# DSKY_DISP.net
KiCad netlist of a schematic drawn in EAGLE
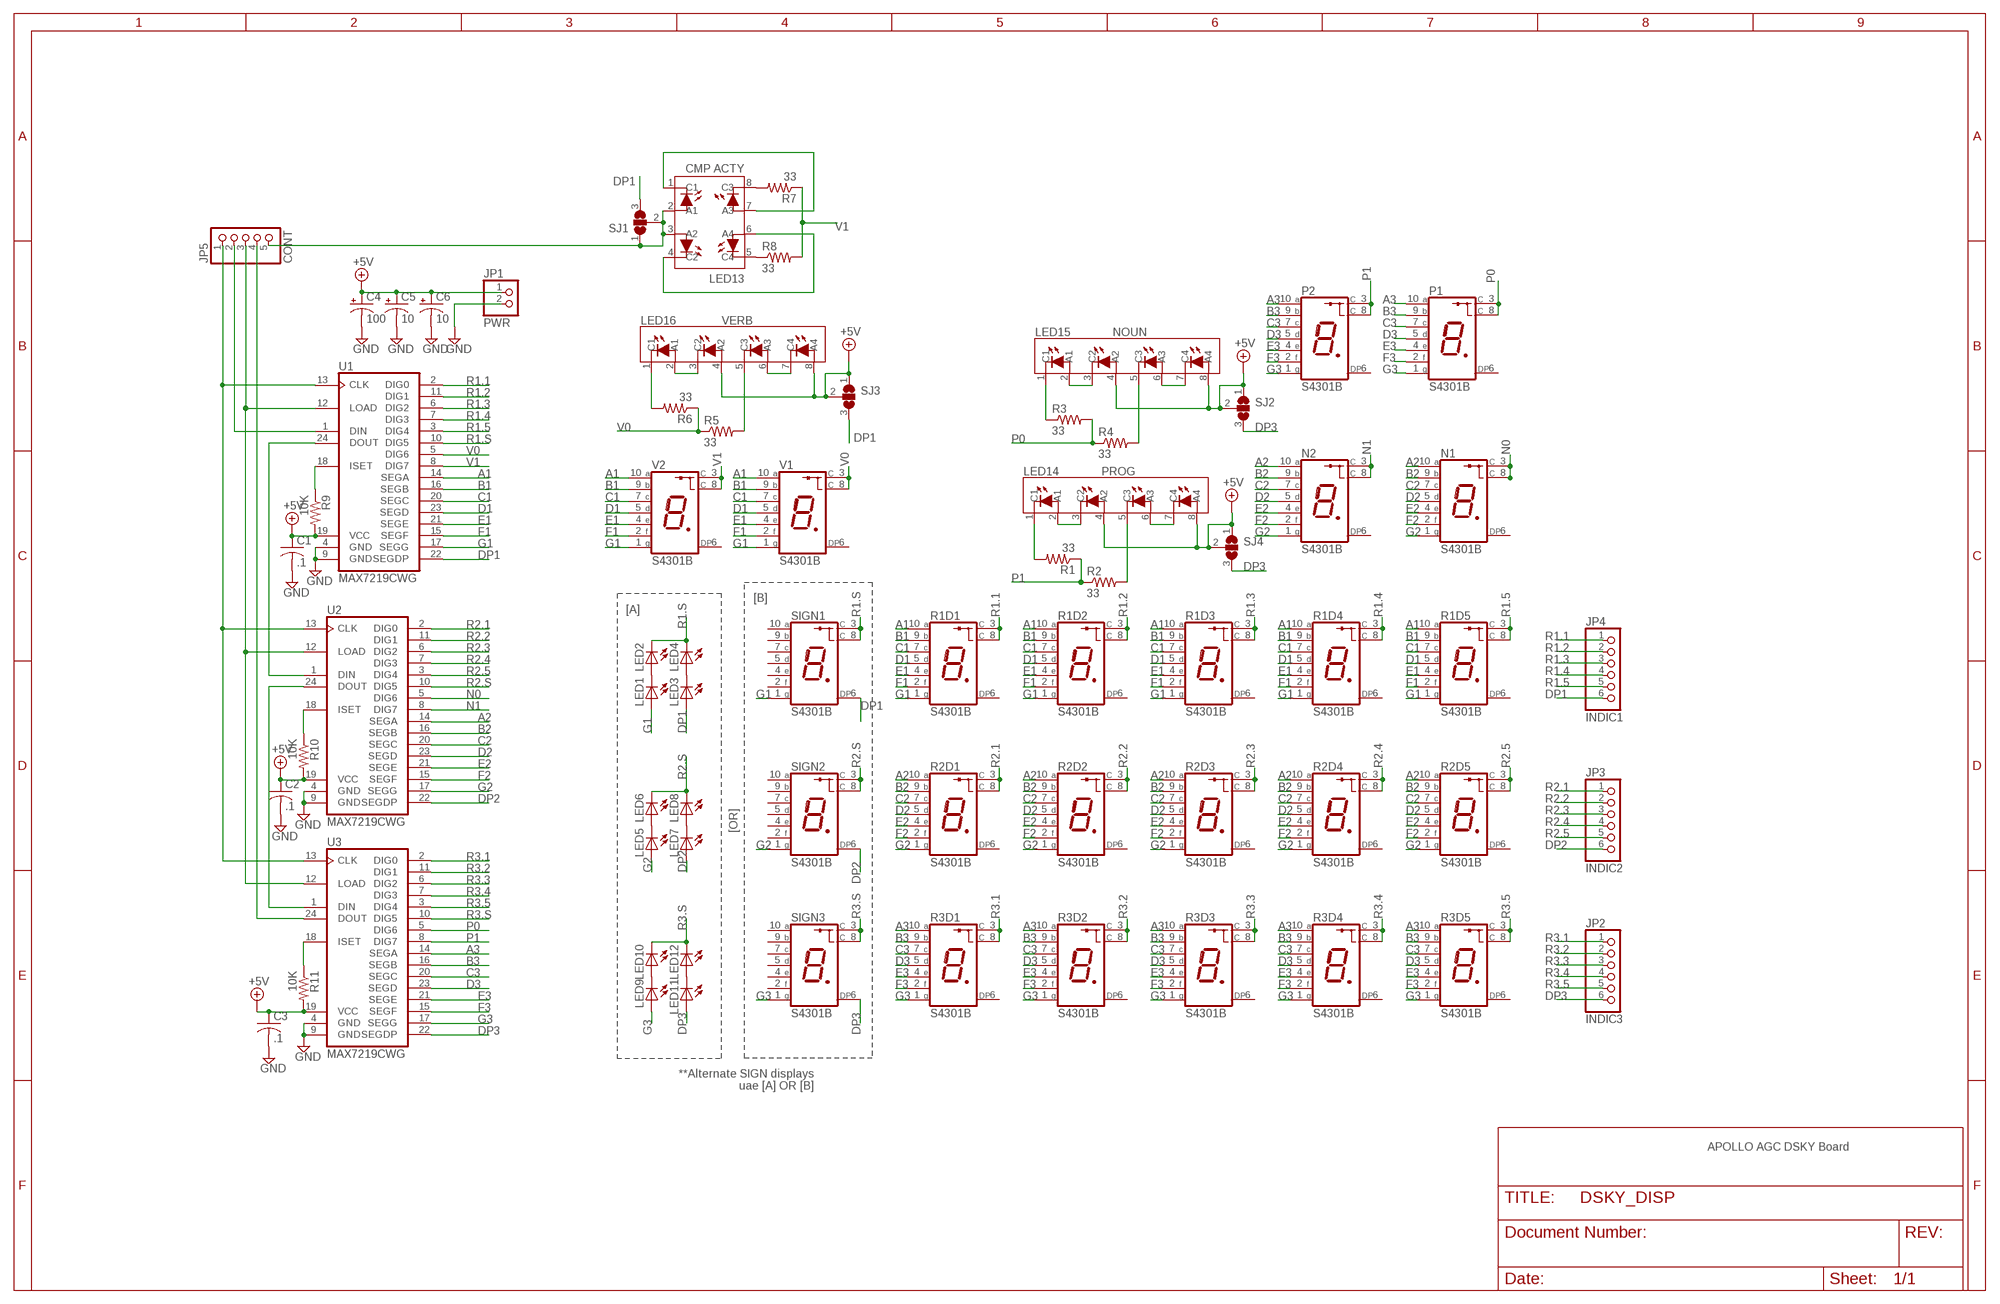
[diagram p0: schematic, sheet 1]

(export (version "E")
  (design (tool "Eeschema 10.0.6"))
  (components
    (comp (ref "C1")
      (value ".1")
      (footprint "eagle-import:C025-030X050")
      (libsource (lib "eagle-import") (part "C-US025-030X050"))
    )
    (comp (ref "C2")
      (value ".1")
      (footprint "eagle-import:C025-030X050")
      (libsource (lib "eagle-import") (part "C-US025-030X050"))
    )
    (comp (ref "C3")
      (value ".1")
      (footprint "eagle-import:C025-030X050")
      (libsource (lib "eagle-import") (part "C-US025-030X050"))
    )
    (comp (ref "C4")
      (value "100")
      (footprint "eagle-import:E2,5-6E")
      (libsource (lib "eagle-import") (part "CPOL-USE2,5-6E"))
    )
    (comp (ref "C5")
      (value "10")
      (footprint "eagle-import:E1,8-4")
      (libsource (lib "eagle-import") (part "CPOL-USE1.8-4"))
    )
    (comp (ref "C6")
      (value "10")
      (footprint "eagle-import:E1,8-4")
      (libsource (lib "eagle-import") (part "CPOL-USE1.8-4"))
    )
    (comp (ref "JP1")
      (value "PWR")
      (footprint "eagle-import:1X02")
      (libsource (lib "eagle-import") (part "PINHD-1X2"))
    )
    (comp (ref "JP2")
      (value "INDIC3")
      (footprint "eagle-import:1X06")
      (libsource (lib "eagle-import") (part "PINHD-1X6"))
    )
    (comp (ref "JP3")
      (value "INDIC2")
      (footprint "eagle-import:1X06")
      (libsource (lib "eagle-import") (part "PINHD-1X6"))
    )
    (comp (ref "JP4")
      (value "INDIC1")
      (footprint "eagle-import:1X06")
      (libsource (lib "eagle-import") (part "PINHD-1X6"))
    )
    (comp (ref "JP5")
      (value "CONT")
      (footprint "eagle-import:1X05")
      (libsource (lib "eagle-import") (part "PINHD-1X5"))
    )
    (comp (ref "LED1")
      (value "LEDCHIPLED_0603")
      (footprint "eagle-import:CHIPLED_0603")
      (libsource (lib "eagle-import") (part "LEDCHIPLED_0603"))
    )
    (comp (ref "LED2")
      (value "LEDCHIPLED_0603")
      (footprint "eagle-import:CHIPLED_0603")
      (libsource (lib "eagle-import") (part "LEDCHIPLED_0603"))
    )
    (comp (ref "LED3")
      (value "LEDCHIPLED_0603")
      (footprint "eagle-import:CHIPLED_0603")
      (libsource (lib "eagle-import") (part "LEDCHIPLED_0603"))
    )
    (comp (ref "LED4")
      (value "LEDCHIPLED_0603")
      (footprint "eagle-import:CHIPLED_0603")
      (libsource (lib "eagle-import") (part "LEDCHIPLED_0603"))
    )
    (comp (ref "LED5")
      (value "LEDCHIPLED_0603")
      (footprint "eagle-import:CHIPLED_0603")
      (libsource (lib "eagle-import") (part "LEDCHIPLED_0603"))
    )
    (comp (ref "LED6")
      (value "LEDCHIPLED_0603")
      (footprint "eagle-import:CHIPLED_0603")
      (libsource (lib "eagle-import") (part "LEDCHIPLED_0603"))
    )
    (comp (ref "LED7")
      (value "LEDCHIPLED_0603")
      (footprint "eagle-import:CHIPLED_0603")
      (libsource (lib "eagle-import") (part "LEDCHIPLED_0603"))
    )
    (comp (ref "LED8")
      (value "LEDCHIPLED_0603")
      (footprint "eagle-import:CHIPLED_0603")
      (libsource (lib "eagle-import") (part "LEDCHIPLED_0603"))
    )
    (comp (ref "LED9")
      (value "LEDCHIPLED_0603")
      (footprint "eagle-import:CHIPLED_0603")
      (libsource (lib "eagle-import") (part "LEDCHIPLED_0603"))
    )
    (comp (ref "LED10")
      (value "LEDCHIPLED_0603")
      (footprint "eagle-import:CHIPLED_0603")
      (libsource (lib "eagle-import") (part "LEDCHIPLED_0603"))
    )
    (comp (ref "LED11")
      (value "LEDCHIPLED_0603")
      (footprint "eagle-import:CHIPLED_0603")
      (libsource (lib "eagle-import") (part "LEDCHIPLED_0603"))
    )
    (comp (ref "LED12")
      (value "LEDCHIPLED_0603")
      (footprint "eagle-import:CHIPLED_0603")
      (libsource (lib "eagle-import") (part "LEDCHIPLED_0603"))
    )
    (comp (ref "LED13")
      (value "CMP ACTY")
      (footprint "eagle-import:SOCKET-08")
      (libsource (lib "eagle-import") (part "HCLP-HLMP-2855"))
    )
    (comp (ref "LED14")
      (value "PROG")
      (footprint "eagle-import:SIP-08")
      (libsource (lib "eagle-import") (part "HLMP-2655"))
    )
    (comp (ref "LED15")
      (value "NOUN")
      (footprint "eagle-import:SIP-08")
      (libsource (lib "eagle-import") (part "HLMP-2655"))
    )
    (comp (ref "LED16")
      (value "VERB")
      (footprint "eagle-import:SIP-08")
      (libsource (lib "eagle-import") (part "HLMP-2655"))
    )
    (comp (ref "N1")
      (value "S4301B")
      (footprint "eagle-import:S4301B")
      (libsource (lib "eagle-import") (part "S4301B"))
    )
    (comp (ref "N2")
      (value "S4301B")
      (footprint "eagle-import:S4301B")
      (libsource (lib "eagle-import") (part "S4301B"))
    )
    (comp (ref "P1")
      (value "S4301B")
      (footprint "eagle-import:S4301B")
      (libsource (lib "eagle-import") (part "S4301B"))
    )
    (comp (ref "P2")
      (value "S4301B")
      (footprint "eagle-import:S4301B")
      (libsource (lib "eagle-import") (part "S4301B"))
    )
    (comp (ref "R1")
      (value "33")
      (footprint "eagle-import:0207_10")
      (libsource (lib "eagle-import") (part "R-US_0207/10"))
    )
    (comp (ref "R1D1")
      (value "S4301B")
      (footprint "eagle-import:S4301B")
      (libsource (lib "eagle-import") (part "S4301B"))
    )
    (comp (ref "R1D2")
      (value "S4301B")
      (footprint "eagle-import:S4301B")
      (libsource (lib "eagle-import") (part "S4301B"))
    )
    (comp (ref "R1D3")
      (value "S4301B")
      (footprint "eagle-import:S4301B")
      (libsource (lib "eagle-import") (part "S4301B"))
    )
    (comp (ref "R1D4")
      (value "S4301B")
      (footprint "eagle-import:S4301B")
      (libsource (lib "eagle-import") (part "S4301B"))
    )
    (comp (ref "R1D5")
      (value "S4301B")
      (footprint "eagle-import:S4301B")
      (libsource (lib "eagle-import") (part "S4301B"))
    )
    (comp (ref "R2")
      (value "33")
      (footprint "eagle-import:0207_10")
      (libsource (lib "eagle-import") (part "R-US_0207/10"))
    )
    (comp (ref "R2D1")
      (value "S4301B")
      (footprint "eagle-import:S4301B")
      (libsource (lib "eagle-import") (part "S4301B"))
    )
    (comp (ref "R2D2")
      (value "S4301B")
      (footprint "eagle-import:S4301B")
      (libsource (lib "eagle-import") (part "S4301B"))
    )
    (comp (ref "R2D3")
      (value "S4301B")
      (footprint "eagle-import:S4301B")
      (libsource (lib "eagle-import") (part "S4301B"))
    )
    (comp (ref "R2D4")
      (value "S4301B")
      (footprint "eagle-import:S4301B")
      (libsource (lib "eagle-import") (part "S4301B"))
    )
    (comp (ref "R2D5")
      (value "S4301B")
      (footprint "eagle-import:S4301B")
      (libsource (lib "eagle-import") (part "S4301B"))
    )
    (comp (ref "R3")
      (value "33")
      (footprint "eagle-import:0207_10")
      (libsource (lib "eagle-import") (part "R-US_0207/10"))
    )
    (comp (ref "R3D1")
      (value "S4301B")
      (footprint "eagle-import:S4301B")
      (libsource (lib "eagle-import") (part "S4301B"))
    )
    (comp (ref "R3D2")
      (value "S4301B")
      (footprint "eagle-import:S4301B")
      (libsource (lib "eagle-import") (part "S4301B"))
    )
    (comp (ref "R3D3")
      (value "S4301B")
      (footprint "eagle-import:S4301B")
      (libsource (lib "eagle-import") (part "S4301B"))
    )
    (comp (ref "R3D4")
      (value "S4301B")
      (footprint "eagle-import:S4301B")
      (libsource (lib "eagle-import") (part "S4301B"))
    )
    (comp (ref "R3D5")
      (value "S4301B")
      (footprint "eagle-import:S4301B")
      (libsource (lib "eagle-import") (part "S4301B"))
    )
    (comp (ref "R4")
      (value "33")
      (footprint "eagle-import:0207_10")
      (libsource (lib "eagle-import") (part "R-US_0207/10"))
    )
    (comp (ref "R5")
      (value "33")
      (footprint "eagle-import:0207_10")
      (libsource (lib "eagle-import") (part "R-US_0207/10"))
    )
    (comp (ref "R6")
      (value "33")
      (footprint "eagle-import:0207_10")
      (libsource (lib "eagle-import") (part "R-US_0207/10"))
    )
    (comp (ref "R7")
      (value "33")
      (footprint "eagle-import:0207_10")
      (libsource (lib "eagle-import") (part "R-US_0207/10"))
    )
    (comp (ref "R8")
      (value "33")
      (footprint "eagle-import:0207_10")
      (libsource (lib "eagle-import") (part "R-US_0207/10"))
    )
    (comp (ref "R9")
      (value "10K")
      (footprint "eagle-import:0207_10")
      (libsource (lib "eagle-import") (part "R-US_0207/10"))
    )
    (comp (ref "R10")
      (value "10K")
      (footprint "eagle-import:0207_10")
      (libsource (lib "eagle-import") (part "R-US_0207/10"))
    )
    (comp (ref "R11")
      (value "10K")
      (footprint "eagle-import:0207_10")
      (libsource (lib "eagle-import") (part "R-US_0207/10"))
    )
    (comp (ref "SIGN1")
      (value "S4301B")
      (footprint "eagle-import:S4301B")
      (libsource (lib "eagle-import") (part "S4301B"))
    )
    (comp (ref "SIGN2")
      (value "S4301B")
      (footprint "eagle-import:S4301B")
      (libsource (lib "eagle-import") (part "S4301B"))
    )
    (comp (ref "SIGN3")
      (value "S4301B")
      (footprint "eagle-import:S4301B")
      (libsource (lib "eagle-import") (part "S4301B"))
    )
    (comp (ref "SJ1")
      (value "SJ2WW")
      (footprint "eagle-import:SJ_2W")
      (libsource (lib "eagle-import") (part "SJ2WW"))
    )
    (comp (ref "SJ2")
      (value "SJ2WW")
      (footprint "eagle-import:SJ_2W")
      (libsource (lib "eagle-import") (part "SJ2WW"))
    )
    (comp (ref "SJ3")
      (value "SJ2WW")
      (footprint "eagle-import:SJ_2W")
      (libsource (lib "eagle-import") (part "SJ2WW"))
    )
    (comp (ref "SJ4")
      (value "SJ2WW")
      (footprint "eagle-import:SJ_2W")
      (libsource (lib "eagle-import") (part "SJ2WW"))
    )
    (comp (ref "U1")
      (value "MAX7219CWG")
      (footprint "eagle-import:SO24W")
      (libsource (lib "eagle-import") (part "MAX7219WGC"))
    )
    (comp (ref "U2")
      (value "MAX7219CWG")
      (footprint "eagle-import:SO24W")
      (libsource (lib "eagle-import") (part "MAX7219WGC"))
    )
    (comp (ref "U3")
      (value "MAX7219CWG")
      (footprint "eagle-import:SO24W")
      (libsource (lib "eagle-import") (part "MAX7219WGC"))
    )
    (comp (ref "V1")
      (value "S4301B")
      (footprint "eagle-import:S4301B")
      (libsource (lib "eagle-import") (part "S4301B"))
    )
    (comp (ref "V2")
      (value "S4301B")
      (footprint "eagle-import:S4301B")
      (libsource (lib "eagle-import") (part "S4301B"))
    )
  )
  (nets
    (net (code "1") (name "+5V") (class "Default")
      (node (ref "C1") (pin "1") (pinfunction "1_1") (pintype "passive"))
      (node (ref "C2") (pin "1") (pinfunction "1_1") (pintype "passive"))
      (node (ref "C3") (pin "1") (pinfunction "1_1") (pintype "passive"))
      (node (ref "C4") (pin "+") (pinfunction "+_+") (pintype "passive"))
      (node (ref "C5") (pin "+") (pinfunction "+_+") (pintype "passive"))
      (node (ref "C6") (pin "+") (pinfunction "+_+") (pintype "passive"))
      (node (ref "JP1") (pin "1") (pinfunction "1_1") (pintype "passive"))
      (node (ref "LED14") (pin "4") (pinfunction "A2_4") (pintype "passive"))
      (node (ref "LED14") (pin "8") (pinfunction "A4_8") (pintype "passive"))
      (node (ref "LED15") (pin "4") (pinfunction "A2_4") (pintype "passive"))
      (node (ref "LED15") (pin "8") (pinfunction "A4_8") (pintype "passive"))
      (node (ref "LED16") (pin "4") (pinfunction "A2_4") (pintype "passive"))
      (node (ref "LED16") (pin "8") (pinfunction "A4_8") (pintype "passive"))
      (node (ref "R10") (pin "2") (pinfunction "2_2") (pintype "passive"))
      (node (ref "R11") (pin "2") (pinfunction "2_2") (pintype "passive"))
      (node (ref "R9") (pin "2") (pinfunction "2_2") (pintype "passive"))
      (node (ref "SJ2") (pin "1") (pinfunction "1_1") (pintype "passive"))
      (node (ref "SJ2") (pin "2") (pinfunction "2_2") (pintype "passive"))
      (node (ref "SJ3") (pin "1") (pinfunction "1_1") (pintype "passive"))
      (node (ref "SJ3") (pin "2") (pinfunction "2_2") (pintype "passive"))
      (node (ref "SJ4") (pin "1") (pinfunction "1_1") (pintype "passive"))
      (node (ref "SJ4") (pin "2") (pinfunction "2_2") (pintype "passive"))
      (node (ref "U1") (pin "19") (pinfunction "VCC_19") (pintype "power_in"))
      (node (ref "U2") (pin "19") (pinfunction "VCC_19") (pintype "power_in"))
      (node (ref "U3") (pin "19") (pinfunction "VCC_19") (pintype "power_in"))
    )
    (net (code "2") (name "/A1") (class "Default")
      (node (ref "R1D1") (pin "10") (pinfunction "A_10") (pintype "passive"))
      (node (ref "R1D2") (pin "10") (pinfunction "A_10") (pintype "passive"))
      (node (ref "R1D3") (pin "10") (pinfunction "A_10") (pintype "passive"))
      (node (ref "R1D4") (pin "10") (pinfunction "A_10") (pintype "passive"))
      (node (ref "R1D5") (pin "10") (pinfunction "A_10") (pintype "passive"))
      (node (ref "U1") (pin "14") (pinfunction "SEGA_14") (pintype "output"))
      (node (ref "V1") (pin "10") (pinfunction "A_10") (pintype "passive"))
      (node (ref "V2") (pin "10") (pinfunction "A_10") (pintype "passive"))
    )
    (net (code "3") (name "/A2") (class "Default")
      (node (ref "N1") (pin "10") (pinfunction "A_10") (pintype "passive"))
      (node (ref "N2") (pin "10") (pinfunction "A_10") (pintype "passive"))
      (node (ref "R2D1") (pin "10") (pinfunction "A_10") (pintype "passive"))
      (node (ref "R2D2") (pin "10") (pinfunction "A_10") (pintype "passive"))
      (node (ref "R2D3") (pin "10") (pinfunction "A_10") (pintype "passive"))
      (node (ref "R2D4") (pin "10") (pinfunction "A_10") (pintype "passive"))
      (node (ref "R2D5") (pin "10") (pinfunction "A_10") (pintype "passive"))
      (node (ref "U2") (pin "14") (pinfunction "SEGA_14") (pintype "output"))
    )
    (net (code "4") (name "/A3") (class "Default")
      (node (ref "P1") (pin "10") (pinfunction "A_10") (pintype "passive"))
      (node (ref "P2") (pin "10") (pinfunction "A_10") (pintype "passive"))
      (node (ref "R3D1") (pin "10") (pinfunction "A_10") (pintype "passive"))
      (node (ref "R3D2") (pin "10") (pinfunction "A_10") (pintype "passive"))
      (node (ref "R3D3") (pin "10") (pinfunction "A_10") (pintype "passive"))
      (node (ref "R3D4") (pin "10") (pinfunction "A_10") (pintype "passive"))
      (node (ref "R3D5") (pin "10") (pinfunction "A_10") (pintype "passive"))
      (node (ref "U3") (pin "14") (pinfunction "SEGA_14") (pintype "output"))
    )
    (net (code "5") (name "/B1") (class "Default")
      (node (ref "R1D1") (pin "9") (pinfunction "B_9") (pintype "passive"))
      (node (ref "R1D2") (pin "9") (pinfunction "B_9") (pintype "passive"))
      (node (ref "R1D3") (pin "9") (pinfunction "B_9") (pintype "passive"))
      (node (ref "R1D4") (pin "9") (pinfunction "B_9") (pintype "passive"))
      (node (ref "R1D5") (pin "9") (pinfunction "B_9") (pintype "passive"))
      (node (ref "U1") (pin "16") (pinfunction "SEGB_16") (pintype "output"))
      (node (ref "V1") (pin "9") (pinfunction "B_9") (pintype "passive"))
      (node (ref "V2") (pin "9") (pinfunction "B_9") (pintype "passive"))
    )
    (net (code "6") (name "/B2") (class "Default")
      (node (ref "N1") (pin "9") (pinfunction "B_9") (pintype "passive"))
      (node (ref "N2") (pin "9") (pinfunction "B_9") (pintype "passive"))
      (node (ref "R2D1") (pin "9") (pinfunction "B_9") (pintype "passive"))
      (node (ref "R2D2") (pin "9") (pinfunction "B_9") (pintype "passive"))
      (node (ref "R2D3") (pin "9") (pinfunction "B_9") (pintype "passive"))
      (node (ref "R2D4") (pin "9") (pinfunction "B_9") (pintype "passive"))
      (node (ref "R2D5") (pin "9") (pinfunction "B_9") (pintype "passive"))
      (node (ref "U2") (pin "16") (pinfunction "SEGB_16") (pintype "output"))
    )
    (net (code "7") (name "/B3") (class "Default")
      (node (ref "P1") (pin "9") (pinfunction "B_9") (pintype "passive"))
      (node (ref "P2") (pin "9") (pinfunction "B_9") (pintype "passive"))
      (node (ref "R3D1") (pin "9") (pinfunction "B_9") (pintype "passive"))
      (node (ref "R3D2") (pin "9") (pinfunction "B_9") (pintype "passive"))
      (node (ref "R3D3") (pin "9") (pinfunction "B_9") (pintype "passive"))
      (node (ref "R3D4") (pin "9") (pinfunction "B_9") (pintype "passive"))
      (node (ref "R3D5") (pin "9") (pinfunction "B_9") (pintype "passive"))
      (node (ref "U3") (pin "16") (pinfunction "SEGB_16") (pintype "output"))
    )
    (net (code "8") (name "/C1") (class "Default")
      (node (ref "R1D1") (pin "7") (pinfunction "C_7") (pintype "passive"))
      (node (ref "R1D2") (pin "7") (pinfunction "C_7") (pintype "passive"))
      (node (ref "R1D3") (pin "7") (pinfunction "C_7") (pintype "passive"))
      (node (ref "R1D4") (pin "7") (pinfunction "C_7") (pintype "passive"))
      (node (ref "R1D5") (pin "7") (pinfunction "C_7") (pintype "passive"))
      (node (ref "U1") (pin "20") (pinfunction "SEGC_20") (pintype "output"))
      (node (ref "V1") (pin "7") (pinfunction "C_7") (pintype "passive"))
      (node (ref "V2") (pin "7") (pinfunction "C_7") (pintype "passive"))
    )
    (net (code "9") (name "/C2") (class "Default")
      (node (ref "N1") (pin "7") (pinfunction "C_7") (pintype "passive"))
      (node (ref "N2") (pin "7") (pinfunction "C_7") (pintype "passive"))
      (node (ref "R2D1") (pin "7") (pinfunction "C_7") (pintype "passive"))
      (node (ref "R2D2") (pin "7") (pinfunction "C_7") (pintype "passive"))
      (node (ref "R2D3") (pin "7") (pinfunction "C_7") (pintype "passive"))
      (node (ref "R2D4") (pin "7") (pinfunction "C_7") (pintype "passive"))
      (node (ref "R2D5") (pin "7") (pinfunction "C_7") (pintype "passive"))
      (node (ref "U2") (pin "20") (pinfunction "SEGC_20") (pintype "output"))
    )
    (net (code "10") (name "/C3") (class "Default")
      (node (ref "P1") (pin "7") (pinfunction "C_7") (pintype "passive"))
      (node (ref "P2") (pin "7") (pinfunction "C_7") (pintype "passive"))
      (node (ref "R3D1") (pin "7") (pinfunction "C_7") (pintype "passive"))
      (node (ref "R3D2") (pin "7") (pinfunction "C_7") (pintype "passive"))
      (node (ref "R3D3") (pin "7") (pinfunction "C_7") (pintype "passive"))
      (node (ref "R3D4") (pin "7") (pinfunction "C_7") (pintype "passive"))
      (node (ref "R3D5") (pin "7") (pinfunction "C_7") (pintype "passive"))
      (node (ref "U3") (pin "20") (pinfunction "SEGC_20") (pintype "output"))
    )
    (net (code "11") (name "/D1") (class "Default")
      (node (ref "R1D1") (pin "5") (pinfunction "D_5") (pintype "passive"))
      (node (ref "R1D2") (pin "5") (pinfunction "D_5") (pintype "passive"))
      (node (ref "R1D3") (pin "5") (pinfunction "D_5") (pintype "passive"))
      (node (ref "R1D4") (pin "5") (pinfunction "D_5") (pintype "passive"))
      (node (ref "R1D5") (pin "5") (pinfunction "D_5") (pintype "passive"))
      (node (ref "U1") (pin "23") (pinfunction "SEGD_23") (pintype "output"))
      (node (ref "V1") (pin "5") (pinfunction "D_5") (pintype "passive"))
      (node (ref "V2") (pin "5") (pinfunction "D_5") (pintype "passive"))
    )
    (net (code "12") (name "/D2") (class "Default")
      (node (ref "N1") (pin "5") (pinfunction "D_5") (pintype "passive"))
      (node (ref "N2") (pin "5") (pinfunction "D_5") (pintype "passive"))
      (node (ref "R2D1") (pin "5") (pinfunction "D_5") (pintype "passive"))
      (node (ref "R2D2") (pin "5") (pinfunction "D_5") (pintype "passive"))
      (node (ref "R2D3") (pin "5") (pinfunction "D_5") (pintype "passive"))
      (node (ref "R2D4") (pin "5") (pinfunction "D_5") (pintype "passive"))
      (node (ref "R2D5") (pin "5") (pinfunction "D_5") (pintype "passive"))
      (node (ref "U2") (pin "23") (pinfunction "SEGD_23") (pintype "output"))
    )
    (net (code "13") (name "/D3") (class "Default")
      (node (ref "P1") (pin "5") (pinfunction "D_5") (pintype "passive"))
      (node (ref "P2") (pin "5") (pinfunction "D_5") (pintype "passive"))
      (node (ref "R3D1") (pin "5") (pinfunction "D_5") (pintype "passive"))
      (node (ref "R3D2") (pin "5") (pinfunction "D_5") (pintype "passive"))
      (node (ref "R3D3") (pin "5") (pinfunction "D_5") (pintype "passive"))
      (node (ref "R3D4") (pin "5") (pinfunction "D_5") (pintype "passive"))
      (node (ref "R3D5") (pin "5") (pinfunction "D_5") (pintype "passive"))
      (node (ref "U3") (pin "23") (pinfunction "SEGD_23") (pintype "output"))
    )
    (net (code "14") (name "/DP1") (class "Default")
      (node (ref "JP4") (pin "6") (pinfunction "6_6") (pintype "passive"))
      (node (ref "LED3") (pin "A") (pinfunction "A_A") (pintype "passive"))
      (node (ref "SIGN1") (pin "6") (pinfunction "DP_6") (pintype "passive"))
      (node (ref "SJ1") (pin "3") (pinfunction "3_3") (pintype "passive"))
      (node (ref "SJ3") (pin "3") (pinfunction "3_3") (pintype "passive"))
      (node (ref "U1") (pin "22") (pinfunction "SEGDP_22") (pintype "output"))
    )
    (net (code "15") (name "/DP2") (class "Default")
      (node (ref "JP3") (pin "6") (pinfunction "6_6") (pintype "passive"))
      (node (ref "LED7") (pin "A") (pinfunction "A_A") (pintype "passive"))
      (node (ref "SIGN2") (pin "6") (pinfunction "DP_6") (pintype "passive"))
      (node (ref "U2") (pin "22") (pinfunction "SEGDP_22") (pintype "output"))
    )
    (net (code "16") (name "/DP3") (class "Default")
      (node (ref "JP2") (pin "6") (pinfunction "6_6") (pintype "passive"))
      (node (ref "LED11") (pin "A") (pinfunction "A_A") (pintype "passive"))
      (node (ref "SIGN3") (pin "6") (pinfunction "DP_6") (pintype "passive"))
      (node (ref "SJ2") (pin "3") (pinfunction "3_3") (pintype "passive"))
      (node (ref "SJ4") (pin "3") (pinfunction "3_3") (pintype "passive"))
      (node (ref "U3") (pin "22") (pinfunction "SEGDP_22") (pintype "output"))
    )
    (net (code "17") (name "/E1") (class "Default")
      (node (ref "R1D1") (pin "4") (pinfunction "E_4") (pintype "passive"))
      (node (ref "R1D2") (pin "4") (pinfunction "E_4") (pintype "passive"))
      (node (ref "R1D3") (pin "4") (pinfunction "E_4") (pintype "passive"))
      (node (ref "R1D4") (pin "4") (pinfunction "E_4") (pintype "passive"))
      (node (ref "R1D5") (pin "4") (pinfunction "E_4") (pintype "passive"))
      (node (ref "U1") (pin "21") (pinfunction "SEGE_21") (pintype "output"))
      (node (ref "V1") (pin "4") (pinfunction "E_4") (pintype "passive"))
      (node (ref "V2") (pin "4") (pinfunction "E_4") (pintype "passive"))
    )
    (net (code "18") (name "/E2") (class "Default")
      (node (ref "N1") (pin "4") (pinfunction "E_4") (pintype "passive"))
      (node (ref "N2") (pin "4") (pinfunction "E_4") (pintype "passive"))
      (node (ref "R2D1") (pin "4") (pinfunction "E_4") (pintype "passive"))
      (node (ref "R2D2") (pin "4") (pinfunction "E_4") (pintype "passive"))
      (node (ref "R2D3") (pin "4") (pinfunction "E_4") (pintype "passive"))
      (node (ref "R2D4") (pin "4") (pinfunction "E_4") (pintype "passive"))
      (node (ref "R2D5") (pin "4") (pinfunction "E_4") (pintype "passive"))
      (node (ref "U2") (pin "21") (pinfunction "SEGE_21") (pintype "output"))
    )
    (net (code "19") (name "/E3") (class "Default")
      (node (ref "P1") (pin "4") (pinfunction "E_4") (pintype "passive"))
      (node (ref "P2") (pin "4") (pinfunction "E_4") (pintype "passive"))
      (node (ref "R3D1") (pin "4") (pinfunction "E_4") (pintype "passive"))
      (node (ref "R3D2") (pin "4") (pinfunction "E_4") (pintype "passive"))
      (node (ref "R3D3") (pin "4") (pinfunction "E_4") (pintype "passive"))
      (node (ref "R3D4") (pin "4") (pinfunction "E_4") (pintype "passive"))
      (node (ref "R3D5") (pin "4") (pinfunction "E_4") (pintype "passive"))
      (node (ref "U3") (pin "21") (pinfunction "SEGE_21") (pintype "output"))
    )
    (net (code "20") (name "/F1") (class "Default")
      (node (ref "R1D1") (pin "2") (pinfunction "F_2") (pintype "passive"))
      (node (ref "R1D2") (pin "2") (pinfunction "F_2") (pintype "passive"))
      (node (ref "R1D3") (pin "2") (pinfunction "F_2") (pintype "passive"))
      (node (ref "R1D4") (pin "2") (pinfunction "F_2") (pintype "passive"))
      (node (ref "R1D5") (pin "2") (pinfunction "F_2") (pintype "passive"))
      (node (ref "U1") (pin "15") (pinfunction "SEGF_15") (pintype "output"))
      (node (ref "V1") (pin "2") (pinfunction "F_2") (pintype "passive"))
      (node (ref "V2") (pin "2") (pinfunction "F_2") (pintype "passive"))
    )
    (net (code "21") (name "/F2") (class "Default")
      (node (ref "N1") (pin "2") (pinfunction "F_2") (pintype "passive"))
      (node (ref "N2") (pin "2") (pinfunction "F_2") (pintype "passive"))
      (node (ref "R2D1") (pin "2") (pinfunction "F_2") (pintype "passive"))
      (node (ref "R2D2") (pin "2") (pinfunction "F_2") (pintype "passive"))
      (node (ref "R2D3") (pin "2") (pinfunction "F_2") (pintype "passive"))
      (node (ref "R2D4") (pin "2") (pinfunction "F_2") (pintype "passive"))
      (node (ref "R2D5") (pin "2") (pinfunction "F_2") (pintype "passive"))
      (node (ref "U2") (pin "15") (pinfunction "SEGF_15") (pintype "output"))
    )
    (net (code "22") (name "/F3") (class "Default")
      (node (ref "P1") (pin "2") (pinfunction "F_2") (pintype "passive"))
      (node (ref "P2") (pin "2") (pinfunction "F_2") (pintype "passive"))
      (node (ref "R3D1") (pin "2") (pinfunction "F_2") (pintype "passive"))
      (node (ref "R3D2") (pin "2") (pinfunction "F_2") (pintype "passive"))
      (node (ref "R3D3") (pin "2") (pinfunction "F_2") (pintype "passive"))
      (node (ref "R3D4") (pin "2") (pinfunction "F_2") (pintype "passive"))
      (node (ref "R3D5") (pin "2") (pinfunction "F_2") (pintype "passive"))
      (node (ref "U3") (pin "15") (pinfunction "SEGF_15") (pintype "output"))
    )
    (net (code "23") (name "/G1") (class "Default")
      (node (ref "LED1") (pin "A") (pinfunction "A_A") (pintype "passive"))
      (node (ref "R1D1") (pin "1") (pinfunction "G_1") (pintype "passive"))
      (node (ref "R1D2") (pin "1") (pinfunction "G_1") (pintype "passive"))
      (node (ref "R1D3") (pin "1") (pinfunction "G_1") (pintype "passive"))
      (node (ref "R1D4") (pin "1") (pinfunction "G_1") (pintype "passive"))
      (node (ref "R1D5") (pin "1") (pinfunction "G_1") (pintype "passive"))
      (node (ref "SIGN1") (pin "1") (pinfunction "G_1") (pintype "passive"))
      (node (ref "U1") (pin "17") (pinfunction "SEGG_17") (pintype "output"))
      (node (ref "V1") (pin "1") (pinfunction "G_1") (pintype "passive"))
      (node (ref "V2") (pin "1") (pinfunction "G_1") (pintype "passive"))
    )
    (net (code "24") (name "/G2") (class "Default")
      (node (ref "LED5") (pin "A") (pinfunction "A_A") (pintype "passive"))
      (node (ref "N1") (pin "1") (pinfunction "G_1") (pintype "passive"))
      (node (ref "N2") (pin "1") (pinfunction "G_1") (pintype "passive"))
      (node (ref "R2D1") (pin "1") (pinfunction "G_1") (pintype "passive"))
      (node (ref "R2D2") (pin "1") (pinfunction "G_1") (pintype "passive"))
      (node (ref "R2D3") (pin "1") (pinfunction "G_1") (pintype "passive"))
      (node (ref "R2D4") (pin "1") (pinfunction "G_1") (pintype "passive"))
      (node (ref "R2D5") (pin "1") (pinfunction "G_1") (pintype "passive"))
      (node (ref "SIGN2") (pin "1") (pinfunction "G_1") (pintype "passive"))
      (node (ref "U2") (pin "17") (pinfunction "SEGG_17") (pintype "output"))
    )
    (net (code "25") (name "/G3") (class "Default")
      (node (ref "LED9") (pin "A") (pinfunction "A_A") (pintype "passive"))
      (node (ref "P1") (pin "1") (pinfunction "G_1") (pintype "passive"))
      (node (ref "P2") (pin "1") (pinfunction "G_1") (pintype "passive"))
      (node (ref "R3D1") (pin "1") (pinfunction "G_1") (pintype "passive"))
      (node (ref "R3D2") (pin "1") (pinfunction "G_1") (pintype "passive"))
      (node (ref "R3D3") (pin "1") (pinfunction "G_1") (pintype "passive"))
      (node (ref "R3D4") (pin "1") (pinfunction "G_1") (pintype "passive"))
      (node (ref "R3D5") (pin "1") (pinfunction "G_1") (pintype "passive"))
      (node (ref "SIGN3") (pin "1") (pinfunction "G_1") (pintype "passive"))
      (node (ref "U3") (pin "17") (pinfunction "SEGG_17") (pintype "output"))
    )
    (net (code "26") (name "/N0") (class "Default")
      (node (ref "N1") (pin "3") (pinfunction "C_3") (pintype "passive"))
      (node (ref "N1") (pin "8") (pinfunction "C_8") (pintype "passive"))
      (node (ref "U2") (pin "5") (pinfunction "DIG6_5") (pintype "output"))
    )
    (net (code "27") (name "/N1") (class "Default")
      (node (ref "N2") (pin "3") (pinfunction "C_3") (pintype "passive"))
      (node (ref "N2") (pin "8") (pinfunction "C_8") (pintype "passive"))
      (node (ref "U2") (pin "8") (pinfunction "DIG7_8") (pintype "output"))
    )
    (net (code "28") (name "/P0") (class "Default")
      (node (ref "P1") (pin "3") (pinfunction "C_3") (pintype "passive"))
      (node (ref "P1") (pin "8") (pinfunction "C_8") (pintype "passive"))
      (node (ref "R3") (pin "2") (pinfunction "2_2") (pintype "passive"))
      (node (ref "R4") (pin "1") (pinfunction "1_1") (pintype "passive"))
      (node (ref "U3") (pin "5") (pinfunction "DIG6_5") (pintype "output"))
    )
    (net (code "29") (name "/P1") (class "Default")
      (node (ref "P2") (pin "3") (pinfunction "C_3") (pintype "passive"))
      (node (ref "P2") (pin "8") (pinfunction "C_8") (pintype "passive"))
      (node (ref "R1") (pin "1") (pinfunction "1_1") (pintype "passive"))
      (node (ref "R2") (pin "1") (pinfunction "1_1") (pintype "passive"))
      (node (ref "U3") (pin "8") (pinfunction "DIG7_8") (pintype "output"))
    )
    (net (code "30") (name "/R1.1") (class "Default")
      (node (ref "JP4") (pin "1") (pinfunction "1_1") (pintype "passive"))
      (node (ref "R1D1") (pin "3") (pinfunction "C_3") (pintype "passive"))
      (node (ref "R1D1") (pin "8") (pinfunction "C_8") (pintype "passive"))
      (node (ref "U1") (pin "2") (pinfunction "DIG0_2") (pintype "output"))
    )
    (net (code "31") (name "/R1.2") (class "Default")
      (node (ref "JP4") (pin "2") (pinfunction "2_2") (pintype "passive"))
      (node (ref "R1D2") (pin "3") (pinfunction "C_3") (pintype "passive"))
      (node (ref "R1D2") (pin "8") (pinfunction "C_8") (pintype "passive"))
      (node (ref "U1") (pin "11") (pinfunction "DIG1_11") (pintype "output"))
    )
    (net (code "32") (name "/R1.3") (class "Default")
      (node (ref "JP4") (pin "3") (pinfunction "3_3") (pintype "passive"))
      (node (ref "R1D3") (pin "3") (pinfunction "C_3") (pintype "passive"))
      (node (ref "R1D3") (pin "8") (pinfunction "C_8") (pintype "passive"))
      (node (ref "U1") (pin "6") (pinfunction "DIG2_6") (pintype "output"))
    )
    (net (code "33") (name "/R1.4") (class "Default")
      (node (ref "JP4") (pin "4") (pinfunction "4_4") (pintype "passive"))
      (node (ref "R1D4") (pin "3") (pinfunction "C_3") (pintype "passive"))
      (node (ref "R1D4") (pin "8") (pinfunction "C_8") (pintype "passive"))
      (node (ref "U1") (pin "7") (pinfunction "DIG3_7") (pintype "output"))
    )
    (net (code "34") (name "/R1.5") (class "Default")
      (node (ref "JP4") (pin "5") (pinfunction "5_5") (pintype "passive"))
      (node (ref "R1D5") (pin "3") (pinfunction "C_3") (pintype "passive"))
      (node (ref "R1D5") (pin "8") (pinfunction "C_8") (pintype "passive"))
      (node (ref "U1") (pin "3") (pinfunction "DIG4_3") (pintype "output"))
    )
    (net (code "35") (name "/R1.S") (class "Default")
      (node (ref "LED2") (pin "C") (pinfunction "C_C") (pintype "passive"))
      (node (ref "LED4") (pin "C") (pinfunction "C_C") (pintype "passive"))
      (node (ref "SIGN1") (pin "3") (pinfunction "C_3") (pintype "passive"))
      (node (ref "SIGN1") (pin "8") (pinfunction "C_8") (pintype "passive"))
      (node (ref "U1") (pin "10") (pinfunction "DIG5_10") (pintype "output"))
    )
    (net (code "36") (name "/R2.1") (class "Default")
      (node (ref "JP3") (pin "1") (pinfunction "1_1") (pintype "passive"))
      (node (ref "R2D1") (pin "3") (pinfunction "C_3") (pintype "passive"))
      (node (ref "R2D1") (pin "8") (pinfunction "C_8") (pintype "passive"))
      (node (ref "U2") (pin "2") (pinfunction "DIG0_2") (pintype "output"))
    )
    (net (code "37") (name "/R2.2") (class "Default")
      (node (ref "JP3") (pin "2") (pinfunction "2_2") (pintype "passive"))
      (node (ref "R2D2") (pin "3") (pinfunction "C_3") (pintype "passive"))
      (node (ref "R2D2") (pin "8") (pinfunction "C_8") (pintype "passive"))
      (node (ref "U2") (pin "11") (pinfunction "DIG1_11") (pintype "output"))
    )
    (net (code "38") (name "/R2.3") (class "Default")
      (node (ref "JP3") (pin "3") (pinfunction "3_3") (pintype "passive"))
      (node (ref "R2D3") (pin "3") (pinfunction "C_3") (pintype "passive"))
      (node (ref "R2D3") (pin "8") (pinfunction "C_8") (pintype "passive"))
      (node (ref "U2") (pin "6") (pinfunction "DIG2_6") (pintype "output"))
    )
    (net (code "39") (name "/R2.4") (class "Default")
      (node (ref "JP3") (pin "4") (pinfunction "4_4") (pintype "passive"))
      (node (ref "R2D4") (pin "3") (pinfunction "C_3") (pintype "passive"))
      (node (ref "R2D4") (pin "8") (pinfunction "C_8") (pintype "passive"))
      (node (ref "U2") (pin "7") (pinfunction "DIG3_7") (pintype "output"))
    )
    (net (code "40") (name "/R2.5") (class "Default")
      (node (ref "JP3") (pin "5") (pinfunction "5_5") (pintype "passive"))
      (node (ref "R2D5") (pin "3") (pinfunction "C_3") (pintype "passive"))
      (node (ref "R2D5") (pin "8") (pinfunction "C_8") (pintype "passive"))
      (node (ref "U2") (pin "3") (pinfunction "DIG4_3") (pintype "output"))
    )
    (net (code "41") (name "/R2.S") (class "Default")
      (node (ref "LED6") (pin "C") (pinfunction "C_C") (pintype "passive"))
      (node (ref "LED8") (pin "C") (pinfunction "C_C") (pintype "passive"))
      (node (ref "SIGN2") (pin "3") (pinfunction "C_3") (pintype "passive"))
      (node (ref "SIGN2") (pin "8") (pinfunction "C_8") (pintype "passive"))
      (node (ref "U2") (pin "10") (pinfunction "DIG5_10") (pintype "output"))
    )
    (net (code "42") (name "/R3.1") (class "Default")
      (node (ref "JP2") (pin "1") (pinfunction "1_1") (pintype "passive"))
      (node (ref "R3D1") (pin "3") (pinfunction "C_3") (pintype "passive"))
      (node (ref "R3D1") (pin "8") (pinfunction "C_8") (pintype "passive"))
      (node (ref "U3") (pin "2") (pinfunction "DIG0_2") (pintype "output"))
    )
    (net (code "43") (name "/R3.2") (class "Default")
      (node (ref "JP2") (pin "2") (pinfunction "2_2") (pintype "passive"))
      (node (ref "R3D2") (pin "3") (pinfunction "C_3") (pintype "passive"))
      (node (ref "R3D2") (pin "8") (pinfunction "C_8") (pintype "passive"))
      (node (ref "U3") (pin "11") (pinfunction "DIG1_11") (pintype "output"))
    )
    (net (code "44") (name "/R3.3") (class "Default")
      (node (ref "JP2") (pin "3") (pinfunction "3_3") (pintype "passive"))
      (node (ref "R3D3") (pin "3") (pinfunction "C_3") (pintype "passive"))
      (node (ref "R3D3") (pin "8") (pinfunction "C_8") (pintype "passive"))
      (node (ref "U3") (pin "6") (pinfunction "DIG2_6") (pintype "output"))
    )
    (net (code "45") (name "/R3.4") (class "Default")
      (node (ref "JP2") (pin "4") (pinfunction "4_4") (pintype "passive"))
      (node (ref "R3D4") (pin "3") (pinfunction "C_3") (pintype "passive"))
      (node (ref "R3D4") (pin "8") (pinfunction "C_8") (pintype "passive"))
      (node (ref "U3") (pin "7") (pinfunction "DIG3_7") (pintype "output"))
    )
    (net (code "46") (name "/R3.5") (class "Default")
      (node (ref "JP2") (pin "5") (pinfunction "5_5") (pintype "passive"))
      (node (ref "R3D5") (pin "3") (pinfunction "C_3") (pintype "passive"))
      (node (ref "R3D5") (pin "8") (pinfunction "C_8") (pintype "passive"))
      (node (ref "U3") (pin "3") (pinfunction "DIG4_3") (pintype "output"))
    )
    (net (code "47") (name "/R3.S") (class "Default")
      (node (ref "LED10") (pin "C") (pinfunction "C_C") (pintype "passive"))
      (node (ref "LED12") (pin "C") (pinfunction "C_C") (pintype "passive"))
      (node (ref "SIGN3") (pin "3") (pinfunction "C_3") (pintype "passive"))
      (node (ref "SIGN3") (pin "8") (pinfunction "C_8") (pintype "passive"))
      (node (ref "U3") (pin "10") (pinfunction "DIG5_10") (pintype "output"))
    )
    (net (code "48") (name "/V0") (class "Default")
      (node (ref "R5") (pin "1") (pinfunction "1_1") (pintype "passive"))
      (node (ref "R6") (pin "1") (pinfunction "1_1") (pintype "passive"))
      (node (ref "U1") (pin "5") (pinfunction "DIG6_5") (pintype "output"))
      (node (ref "V1") (pin "3") (pinfunction "C_3") (pintype "passive"))
      (node (ref "V1") (pin "8") (pinfunction "C_8") (pintype "passive"))
    )
    (net (code "49") (name "/V1") (class "Default")
      (node (ref "R7") (pin "1") (pinfunction "1_1") (pintype "passive"))
      (node (ref "R8") (pin "2") (pinfunction "2_2") (pintype "passive"))
      (node (ref "U1") (pin "8") (pinfunction "DIG7_8") (pintype "output"))
      (node (ref "V2") (pin "3") (pinfunction "C_3") (pintype "passive"))
      (node (ref "V2") (pin "8") (pinfunction "C_8") (pintype "passive"))
    )
    (net (code "50") (name "GND") (class "Default")
      (node (ref "C1") (pin "2") (pinfunction "2_2") (pintype "passive"))
      (node (ref "C2") (pin "2") (pinfunction "2_2") (pintype "passive"))
      (node (ref "C3") (pin "2") (pinfunction "2_2") (pintype "passive"))
      (node (ref "C4") (pin "-") (pinfunction "-_-") (pintype "passive"))
      (node (ref "C5") (pin "-") (pinfunction "-_-") (pintype "passive"))
      (node (ref "C6") (pin "-") (pinfunction "-_-") (pintype "passive"))
      (node (ref "JP1") (pin "2") (pinfunction "2_2") (pintype "passive"))
      (node (ref "U1") (pin "4") (pinfunction "GND_4") (pintype "power_in"))
      (node (ref "U1") (pin "9") (pinfunction "GND_9") (pintype "power_in"))
      (node (ref "U2") (pin "4") (pinfunction "GND_4") (pintype "power_in"))
      (node (ref "U2") (pin "9") (pinfunction "GND_9") (pintype "power_in"))
      (node (ref "U3") (pin "4") (pinfunction "GND_4") (pintype "power_in"))
      (node (ref "U3") (pin "9") (pinfunction "GND_9") (pintype "power_in"))
    )
    (net (code "51") (name "Net-(LED1-PadC)") (class "Default")
      (node (ref "LED1") (pin "C") (pinfunction "C_C") (pintype "passive"))
      (node (ref "LED2") (pin "A") (pinfunction "A_A") (pintype "passive"))
    )
    (net (code "52") (name "Net-(LED3-PadC)") (class "Default")
      (node (ref "LED3") (pin "C") (pinfunction "C_C") (pintype "passive"))
      (node (ref "LED4") (pin "A") (pinfunction "A_A") (pintype "passive"))
    )
    (net (code "53") (name "Net-(LED5-PadC)") (class "Default")
      (node (ref "LED5") (pin "C") (pinfunction "C_C") (pintype "passive"))
      (node (ref "LED6") (pin "A") (pinfunction "A_A") (pintype "passive"))
    )
    (net (code "54") (name "Net-(LED7-PadC)") (class "Default")
      (node (ref "LED7") (pin "C") (pinfunction "C_C") (pintype "passive"))
      (node (ref "LED8") (pin "A") (pinfunction "A_A") (pintype "passive"))
    )
    (net (code "55") (name "Net-(LED10-PadA)") (class "Default")
      (node (ref "LED10") (pin "A") (pinfunction "A_A") (pintype "passive"))
      (node (ref "LED9") (pin "C") (pinfunction "C_C") (pintype "passive"))
    )
    (net (code "56") (name "Net-(LED11-PadC)") (class "Default")
      (node (ref "LED11") (pin "C") (pinfunction "C_C") (pintype "passive"))
      (node (ref "LED12") (pin "A") (pinfunction "A_A") (pintype "passive"))
    )
    (net (code "57") (name "Net-(LED13-A1)") (class "Default")
      (node (ref "JP5") (pin "5") (pinfunction "5_5") (pintype "passive"))
      (node (ref "LED13") (pin "2") (pinfunction "A1_2") (pintype "passive"))
      (node (ref "LED13") (pin "3") (pinfunction "A2_3") (pintype "passive"))
      (node (ref "SJ1") (pin "1") (pinfunction "1_1") (pintype "passive"))
      (node (ref "SJ1") (pin "2") (pinfunction "2_2") (pintype "passive"))
    )
    (net (code "58") (name "Net-(LED13-A3)") (class "Default")
      (node (ref "LED13") (pin "1") (pinfunction "C1_1") (pintype "passive"))
      (node (ref "LED13") (pin "7") (pinfunction "A3_7") (pintype "passive"))
    )
    (net (code "59") (name "Net-(LED13-A4)") (class "Default")
      (node (ref "LED13") (pin "4") (pinfunction "C2_4") (pintype "passive"))
      (node (ref "LED13") (pin "6") (pinfunction "A4_6") (pintype "passive"))
    )
    (net (code "60") (name "Net-(LED13-C3)") (class "Default")
      (node (ref "LED13") (pin "8") (pinfunction "C3_8") (pintype "passive"))
      (node (ref "R7") (pin "2") (pinfunction "2_2") (pintype "passive"))
    )
    (net (code "61") (name "Net-(LED13-C4)") (class "Default")
      (node (ref "LED13") (pin "5") (pinfunction "C4_5") (pintype "passive"))
      (node (ref "R8") (pin "1") (pinfunction "1_1") (pintype "passive"))
    )
    (net (code "62") (name "Net-(LED14-A1)") (class "Default")
      (node (ref "LED14") (pin "2") (pinfunction "A1_2") (pintype "passive"))
      (node (ref "LED14") (pin "3") (pinfunction "C2_3") (pintype "passive"))
    )
    (net (code "63") (name "Net-(LED14-A3)") (class "Default")
      (node (ref "LED14") (pin "6") (pinfunction "A3_6") (pintype "passive"))
      (node (ref "LED14") (pin "7") (pinfunction "C4_7") (pintype "passive"))
    )
    (net (code "64") (name "Net-(LED14-C1)") (class "Default")
      (node (ref "LED14") (pin "1") (pinfunction "C1_1") (pintype "passive"))
      (node (ref "R1") (pin "2") (pinfunction "2_2") (pintype "passive"))
    )
    (net (code "65") (name "Net-(LED14-C3)") (class "Default")
      (node (ref "LED14") (pin "5") (pinfunction "C3_5") (pintype "passive"))
      (node (ref "R2") (pin "2") (pinfunction "2_2") (pintype "passive"))
    )
    (net (code "66") (name "Net-(LED15-A1)") (class "Default")
      (node (ref "LED15") (pin "2") (pinfunction "A1_2") (pintype "passive"))
      (node (ref "LED15") (pin "3") (pinfunction "C2_3") (pintype "passive"))
    )
    (net (code "67") (name "Net-(LED15-A3)") (class "Default")
      (node (ref "LED15") (pin "6") (pinfunction "A3_6") (pintype "passive"))
      (node (ref "LED15") (pin "7") (pinfunction "C4_7") (pintype "passive"))
    )
    (net (code "68") (name "Net-(LED15-C1)") (class "Default")
      (node (ref "LED15") (pin "1") (pinfunction "C1_1") (pintype "passive"))
      (node (ref "R3") (pin "1") (pinfunction "1_1") (pintype "passive"))
    )
    (net (code "69") (name "Net-(LED15-C3)") (class "Default")
      (node (ref "LED15") (pin "5") (pinfunction "C3_5") (pintype "passive"))
      (node (ref "R4") (pin "2") (pinfunction "2_2") (pintype "passive"))
    )
    (net (code "70") (name "Net-(LED16-A1)") (class "Default")
      (node (ref "LED16") (pin "2") (pinfunction "A1_2") (pintype "passive"))
      (node (ref "LED16") (pin "3") (pinfunction "C2_3") (pintype "passive"))
    )
    (net (code "71") (name "Net-(LED16-A3)") (class "Default")
      (node (ref "LED16") (pin "6") (pinfunction "A3_6") (pintype "passive"))
      (node (ref "LED16") (pin "7") (pinfunction "C4_7") (pintype "passive"))
    )
    (net (code "72") (name "Net-(LED16-C1)") (class "Default")
      (node (ref "LED16") (pin "1") (pinfunction "C1_1") (pintype "passive"))
      (node (ref "R6") (pin "2") (pinfunction "2_2") (pintype "passive"))
    )
    (net (code "73") (name "Net-(LED16-C3)") (class "Default")
      (node (ref "LED16") (pin "5") (pinfunction "C3_5") (pintype "passive"))
      (node (ref "R5") (pin "2") (pinfunction "2_2") (pintype "passive"))
    )
    (net (code "74") (name "Net-(U1-CLK)") (class "Default")
      (node (ref "JP5") (pin "1") (pinfunction "1_1") (pintype "passive"))
      (node (ref "U1") (pin "13") (pinfunction "CLK_13") (pintype "input"))
      (node (ref "U2") (pin "13") (pinfunction "CLK_13") (pintype "input"))
      (node (ref "U3") (pin "13") (pinfunction "CLK_13") (pintype "input"))
    )
    (net (code "75") (name "Net-(U1-DIN)") (class "Default")
      (node (ref "JP5") (pin "2") (pinfunction "2_2") (pintype "passive"))
      (node (ref "U1") (pin "1") (pinfunction "DIN_1") (pintype "input"))
    )
    (net (code "76") (name "Net-(U1-DOUT)") (class "Default")
      (node (ref "U1") (pin "24") (pinfunction "DOUT_24") (pintype "output"))
      (node (ref "U2") (pin "1") (pinfunction "DIN_1") (pintype "input"))
    )
    (net (code "77") (name "Net-(U1-ISET)") (class "Default")
      (node (ref "R9") (pin "1") (pinfunction "1_1") (pintype "passive"))
      (node (ref "U1") (pin "18") (pinfunction "ISET_18") (pintype "input"))
    )
    (net (code "78") (name "Net-(U1-LOAD)") (class "Default")
      (node (ref "JP5") (pin "3") (pinfunction "3_3") (pintype "passive"))
      (node (ref "U1") (pin "12") (pinfunction "LOAD_12") (pintype "input"))
      (node (ref "U2") (pin "12") (pinfunction "LOAD_12") (pintype "input"))
      (node (ref "U3") (pin "12") (pinfunction "LOAD_12") (pintype "input"))
    )
    (net (code "79") (name "Net-(U2-DOUT)") (class "Default")
      (node (ref "U2") (pin "24") (pinfunction "DOUT_24") (pintype "output"))
      (node (ref "U3") (pin "1") (pinfunction "DIN_1") (pintype "input"))
    )
    (net (code "80") (name "Net-(U2-ISET)") (class "Default")
      (node (ref "R10") (pin "1") (pinfunction "1_1") (pintype "passive"))
      (node (ref "U2") (pin "18") (pinfunction "ISET_18") (pintype "input"))
    )
    (net (code "81") (name "Net-(U3-DOUT)") (class "Default")
      (node (ref "JP5") (pin "4") (pinfunction "4_4") (pintype "passive"))
      (node (ref "U3") (pin "24") (pinfunction "DOUT_24") (pintype "output"))
    )
    (net (code "82") (name "Net-(U3-ISET)") (class "Default")
      (node (ref "R11") (pin "1") (pinfunction "1_1") (pintype "passive"))
      (node (ref "U3") (pin "18") (pinfunction "ISET_18") (pintype "input"))
    )
    (net (code "83") (name "unconnected-(N1-DP-Pad6)") (class "Default")
      (node (ref "N1") (pin "6") (pinfunction "DP_6") (pintype "passive"))
    )
    (net (code "84") (name "unconnected-(N2-DP-Pad6)") (class "Default")
      (node (ref "N2") (pin "6") (pinfunction "DP_6") (pintype "passive"))
    )
    (net (code "85") (name "unconnected-(P1-DP-Pad6)") (class "Default")
      (node (ref "P1") (pin "6") (pinfunction "DP_6") (pintype "passive"))
    )
    (net (code "86") (name "unconnected-(P2-DP-Pad6)") (class "Default")
      (node (ref "P2") (pin "6") (pinfunction "DP_6") (pintype "passive"))
    )
    (net (code "87") (name "unconnected-(R1D1-DP-Pad6)") (class "Default")
      (node (ref "R1D1") (pin "6") (pinfunction "DP_6") (pintype "passive"))
    )
    (net (code "88") (name "unconnected-(R1D2-DP-Pad6)") (class "Default")
      (node (ref "R1D2") (pin "6") (pinfunction "DP_6") (pintype "passive"))
    )
    (net (code "89") (name "unconnected-(R1D3-DP-Pad6)") (class "Default")
      (node (ref "R1D3") (pin "6") (pinfunction "DP_6") (pintype "passive"))
    )
    (net (code "90") (name "unconnected-(R1D4-DP-Pad6)") (class "Default")
      (node (ref "R1D4") (pin "6") (pinfunction "DP_6") (pintype "passive"))
    )
    (net (code "91") (name "unconnected-(R1D5-DP-Pad6)") (class "Default")
      (node (ref "R1D5") (pin "6") (pinfunction "DP_6") (pintype "passive"))
    )
    (net (code "92") (name "unconnected-(R2D1-DP-Pad6)") (class "Default")
      (node (ref "R2D1") (pin "6") (pinfunction "DP_6") (pintype "passive"))
    )
    (net (code "93") (name "unconnected-(R2D2-DP-Pad6)") (class "Default")
      (node (ref "R2D2") (pin "6") (pinfunction "DP_6") (pintype "passive"))
    )
    (net (code "94") (name "unconnected-(R2D3-DP-Pad6)") (class "Default")
      (node (ref "R2D3") (pin "6") (pinfunction "DP_6") (pintype "passive"))
    )
    (net (code "95") (name "unconnected-(R2D4-DP-Pad6)") (class "Default")
      (node (ref "R2D4") (pin "6") (pinfunction "DP_6") (pintype "passive"))
    )
    (net (code "96") (name "unconnected-(R2D5-DP-Pad6)") (class "Default")
      (node (ref "R2D5") (pin "6") (pinfunction "DP_6") (pintype "passive"))
    )
    (net (code "97") (name "unconnected-(R3D1-DP-Pad6)") (class "Default")
      (node (ref "R3D1") (pin "6") (pinfunction "DP_6") (pintype "passive"))
    )
    (net (code "98") (name "unconnected-(R3D2-DP-Pad6)") (class "Default")
      (node (ref "R3D2") (pin "6") (pinfunction "DP_6") (pintype "passive"))
    )
    (net (code "99") (name "unconnected-(R3D3-DP-Pad6)") (class "Default")
      (node (ref "R3D3") (pin "6") (pinfunction "DP_6") (pintype "passive"))
    )
    (net (code "100") (name "unconnected-(R3D4-DP-Pad6)") (class "Default")
      (node (ref "R3D4") (pin "6") (pinfunction "DP_6") (pintype "passive"))
    )
    (net (code "101") (name "unconnected-(R3D5-DP-Pad6)") (class "Default")
      (node (ref "R3D5") (pin "6") (pinfunction "DP_6") (pintype "passive"))
    )
    (net (code "102") (name "unconnected-(SIGN1-A-Pad10)") (class "Default")
      (node (ref "SIGN1") (pin "10") (pinfunction "A_10") (pintype "passive"))
    )
    (net (code "103") (name "unconnected-(SIGN1-B-Pad9)") (class "Default")
      (node (ref "SIGN1") (pin "9") (pinfunction "B_9") (pintype "passive"))
    )
    (net (code "104") (name "unconnected-(SIGN1-C-Pad7)") (class "Default")
      (node (ref "SIGN1") (pin "7") (pinfunction "C_7") (pintype "passive"))
    )
    (net (code "105") (name "unconnected-(SIGN1-D-Pad5)") (class "Default")
      (node (ref "SIGN1") (pin "5") (pinfunction "D_5") (pintype "passive"))
    )
    (net (code "106") (name "unconnected-(SIGN1-E-Pad4)") (class "Default")
      (node (ref "SIGN1") (pin "4") (pinfunction "E_4") (pintype "passive"))
    )
    (net (code "107") (name "unconnected-(SIGN1-F-Pad2)") (class "Default")
      (node (ref "SIGN1") (pin "2") (pinfunction "F_2") (pintype "passive"))
    )
    (net (code "108") (name "unconnected-(SIGN2-A-Pad10)") (class "Default")
      (node (ref "SIGN2") (pin "10") (pinfunction "A_10") (pintype "passive"))
    )
    (net (code "109") (name "unconnected-(SIGN2-B-Pad9)") (class "Default")
      (node (ref "SIGN2") (pin "9") (pinfunction "B_9") (pintype "passive"))
    )
    (net (code "110") (name "unconnected-(SIGN2-C-Pad7)") (class "Default")
      (node (ref "SIGN2") (pin "7") (pinfunction "C_7") (pintype "passive"))
    )
    (net (code "111") (name "unconnected-(SIGN2-D-Pad5)") (class "Default")
      (node (ref "SIGN2") (pin "5") (pinfunction "D_5") (pintype "passive"))
    )
    (net (code "112") (name "unconnected-(SIGN2-E-Pad4)") (class "Default")
      (node (ref "SIGN2") (pin "4") (pinfunction "E_4") (pintype "passive"))
    )
    (net (code "113") (name "unconnected-(SIGN2-F-Pad2)") (class "Default")
      (node (ref "SIGN2") (pin "2") (pinfunction "F_2") (pintype "passive"))
    )
    (net (code "114") (name "unconnected-(SIGN3-A-Pad10)") (class "Default")
      (node (ref "SIGN3") (pin "10") (pinfunction "A_10") (pintype "passive"))
    )
    (net (code "115") (name "unconnected-(SIGN3-B-Pad9)") (class "Default")
      (node (ref "SIGN3") (pin "9") (pinfunction "B_9") (pintype "passive"))
    )
    (net (code "116") (name "unconnected-(SIGN3-C-Pad7)") (class "Default")
      (node (ref "SIGN3") (pin "7") (pinfunction "C_7") (pintype "passive"))
    )
    (net (code "117") (name "unconnected-(SIGN3-D-Pad5)") (class "Default")
      (node (ref "SIGN3") (pin "5") (pinfunction "D_5") (pintype "passive"))
    )
    (net (code "118") (name "unconnected-(SIGN3-E-Pad4)") (class "Default")
      (node (ref "SIGN3") (pin "4") (pinfunction "E_4") (pintype "passive"))
    )
    (net (code "119") (name "unconnected-(SIGN3-F-Pad2)") (class "Default")
      (node (ref "SIGN3") (pin "2") (pinfunction "F_2") (pintype "passive"))
    )
    (net (code "120") (name "unconnected-(V1-DP-Pad6)") (class "Default")
      (node (ref "V1") (pin "6") (pinfunction "DP_6") (pintype "passive"))
    )
    (net (code "121") (name "unconnected-(V2-DP-Pad6)") (class "Default")
      (node (ref "V2") (pin "6") (pinfunction "DP_6") (pintype "passive"))
    )
  )
)
